# 02_main.net
KiCad netlist of a schematic drawn in Altium Designer
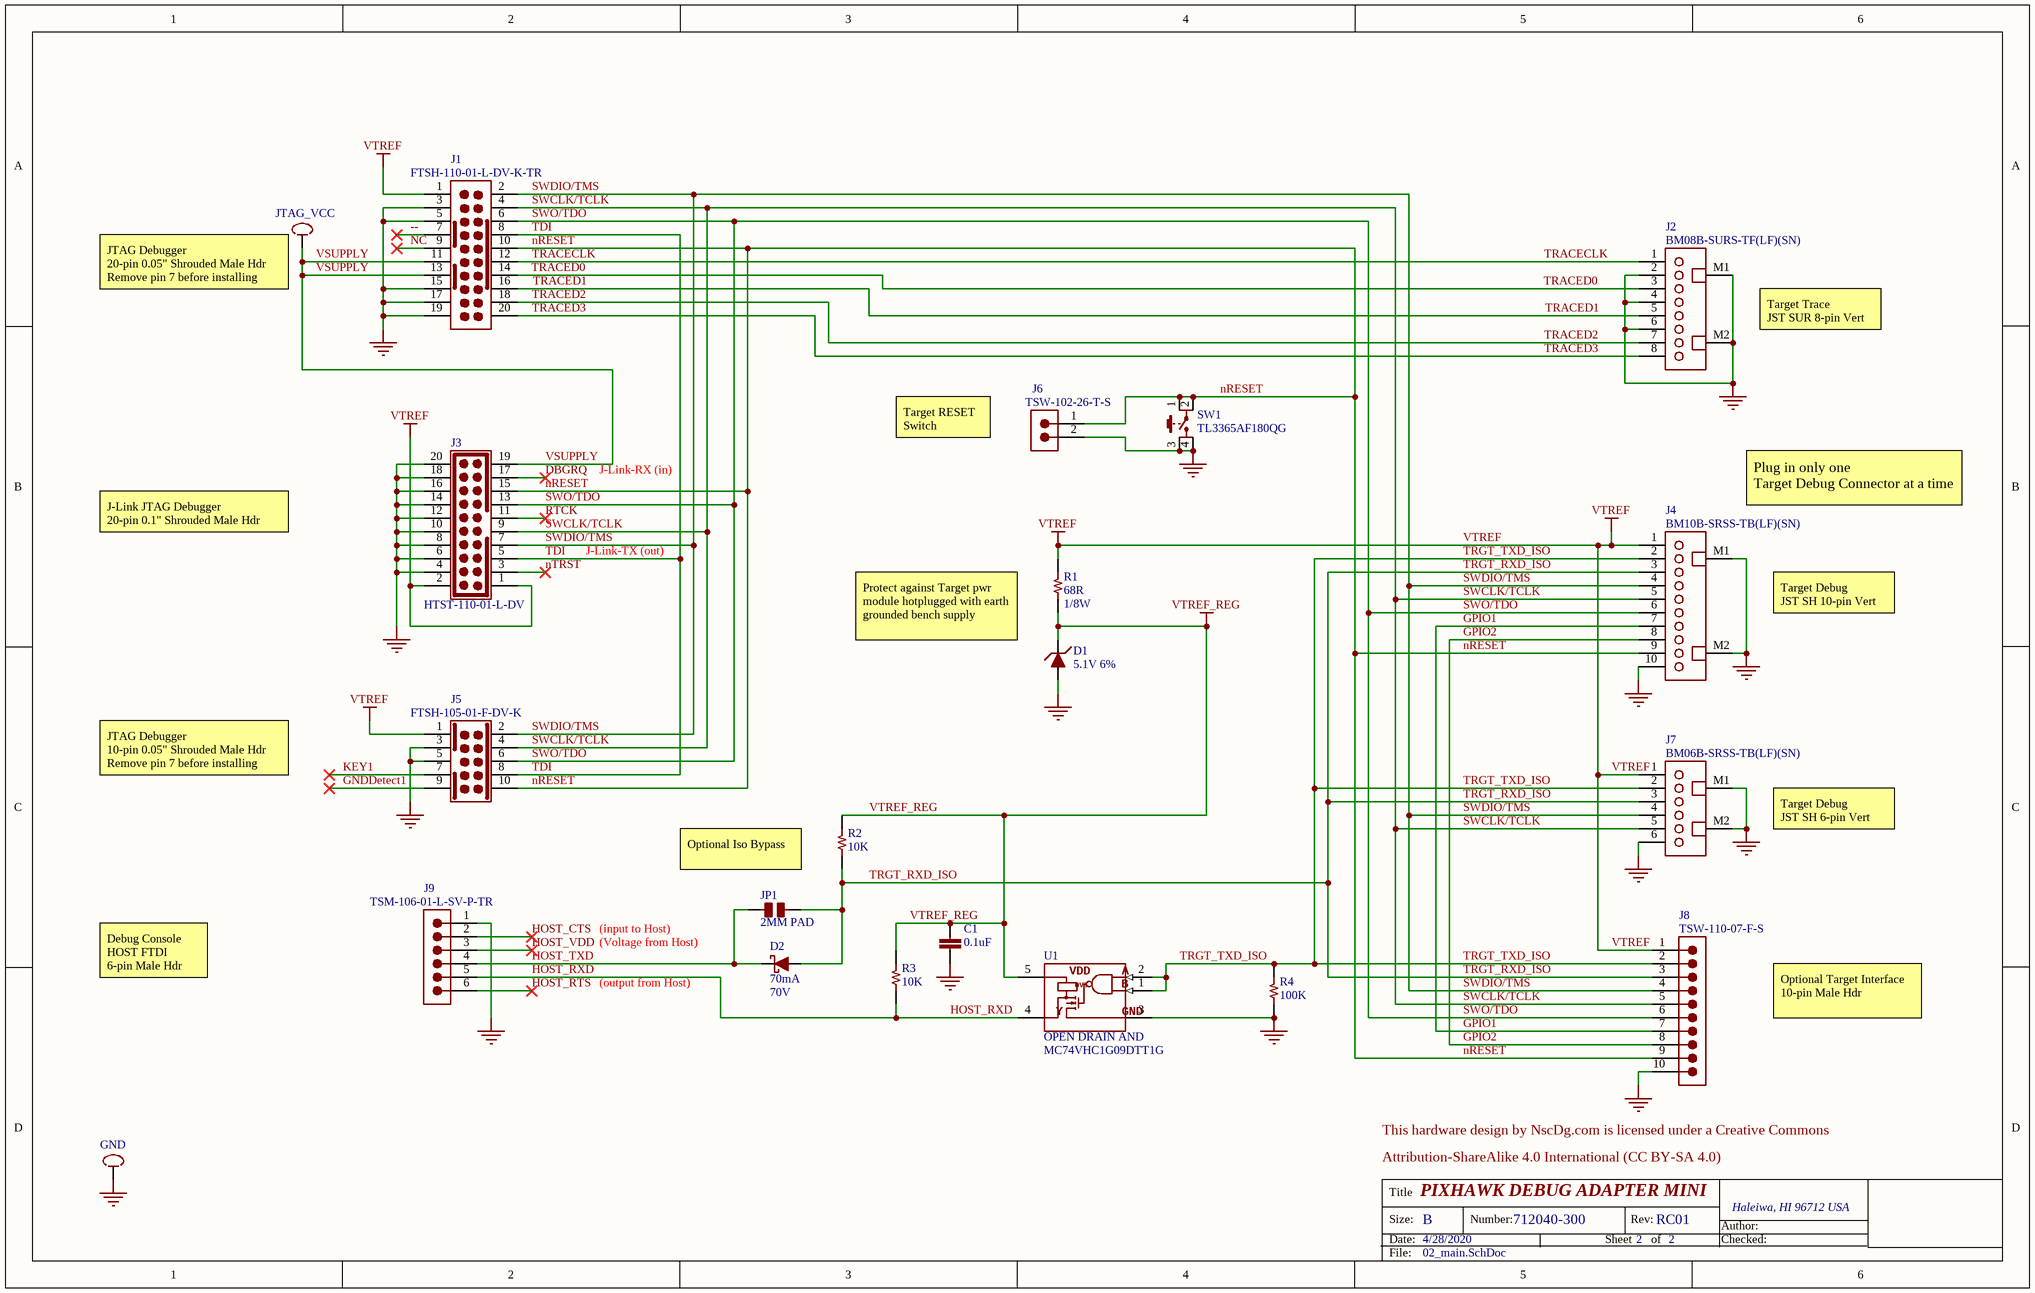
[diagram p0: 02_main.SchDoc]

(export (version "E")
  (design (tool "Eeschema 10.0.6"))
  (components
    (comp (ref "C1")
      (value "0.1uF")
      (footprint "CAPC100X50X56L25N")
      (description "CAP CER 0.1UF 10% 50V X5R 0402")
      (fields
        (field (name "TOLERANCE") "±10%")
        (field (name "MANUFACTURER") "Murata Electronics North America")
      )
      (libsource (lib "My_Integrated_Library") (part "CAP_0U1_50V_X5R_0402"))
    )
    (comp (ref "D1")
      (value "DIODE ZENER 5.1V 225MW SOT23-3")
      (footprint "SOT23-3P95_230X110L30X43N_DIODE")
      (fields
        (field (name "MANUFACTURER") "ON Semiconductor")
        (field (name "MANUFACTURER PART NUMBER") "BZX84C5V1LT3G")
        (field (name "ID") "5.1V 6%")
      )
      (libsource (lib "My_Integrated_Library") (part "DIODE_ZENER_5.1V_SOT23-3"))
    )
    (comp (ref "D2")
      (value "DIODE SCHOTTKY 70V 70MA SOD523")
      (footprint "SODFL120X80X70L30X30")
      (fields
        (field (name "MANUFACTURER") "STMicroelectronics")
        (field (name "MANUFACTURER PART NUMBER") "BAS70KFILM")
        (field (name "CURRENT") "70mA")
        (field (name "VOLTAGE") "70V")
      )
      (libsource (lib "My_Integrated_Library") (part "DIODE_SCHOTTKY_BAS70_SOD523_SMT"))
    )
    (comp (ref "GND")
      (value "TESTPOINT MINIATURE SMD")
      (footprint "KSTN-5015")
      (fields
        (field (name "MANUFACTURER") "Keystone Electronics")
        (field (name "MANUFACTURER PART NUMBER") "5015")
      )
      (libsource (lib "My_Integrated_Library") (part "TESTPOINT_MINIATURE_SMD"))
    )
    (comp (ref "J1")
      (value "CONN_HDR_2X10_VERT_SHROUD_FTSH_1.27MM_SMT")
      (footprint "SAMTEC_FTSH-110-01-L-DV-K-TR")
      (fields
        (field (name "MANUFACTURER") "Samtec Inc.")
        (field (name "MANUFACTURER PART NUMBER") "FTSH-110-01-L-DV-K-TR")
      )
      (libsource (lib "My_Integrated_Library") (part "CONN_HDR_2X10_SHROUD_1.27MM_SMT"))
    )
    (comp (ref "J2")
      (value "CONN HEADER SUR 8POS .8MM VERT SMT")
      (footprint "JST_BM08B-SURS-TFLFSN")
      (fields
        (field (name "MANUFACTURER") "JST Sales America Inc.")
        (field (name "MANUFACTURER PART NUMBER") "BM08B-SURS-TF(LF)(SN)")
      )
      (libsource (lib "My_Integrated_Library") (part "CONN_JST_SUR_8PIN_VERT_SMT"))
    )
    (comp (ref "J3")
      (value "CONN_HDR_2X10_MALE_2.54MM_SHR_SAMTEC_SMD")
      (footprint "SAMTEC_HTST-110-01-F-DV")
      (fields
        (field (name "MANUFACTURER") "Samtec Inc.")
        (field (name "MANUFACTURER PART NUMBER") "HTST-110-01-L-DV")
      )
      (libsource (lib "My_Integrated_Library") (part "CONN_HDR_2X10_MALE_2.54MM_SHR_SAMTEC_SMD"))
    )
    (comp (ref "J4")
      (value "CONN HEADER SH 10POS TOP 1MM TIN")
      (footprint "JST_BM10B-SRSS-TB")
      (fields
        (field (name "MANUFACTURER") "JST Sales America Inc.")
        (field (name "MANUFACTURER PART NUMBER") "BM10B-SRSS-TB(LF)(SN)")
      )
      (libsource (lib "My_Integrated_Library") (part "CONN_JST_SH_10PIN_VERT_SMT"))
    )
    (comp (ref "J5")
      (value "CONN HEADER 10POS DUAL .05\" SMD")
      (footprint "FTSH-105-01-XXX-DV-K")
      (fields
        (field (name "MANUFACTURER") "Samtec Inc.")
        (field (name "MANUFACTURER PART NUMBER") "FTSH-105-01-F-DV-K")
      )
      (libsource (lib "My_Integrated_Library") (part "CONN_HDR_2X5_MALE_1.27MM_SMT"))
    )
    (comp (ref "J6")
      (value "CONN HEADER 2POS 0.100\" (2.54mm) TH")
      (footprint "SMTC-TSW-102-26-XX-S")
      (fields
        (field (name "MANUFACTURER") "Samtec Inc.")
        (field (name "MANUFACTURER PART NUMBER") "TSW-102-26-T-S")
      )
      (libsource (lib "My_Integrated_Library") (part "CONN_HDR_1X2_MALE_2.54MM_TH"))
    )
    (comp (ref "J7")
      (value "CONN HEADER SH 6POS TOP 1MM TIN")
      (footprint "JST_BM06B-SRSS-TB")
      (fields
        (field (name "MANUFACTURER") "JST Sales America Inc.")
        (field (name "MANUFACTURER PART NUMBER") "BM06B-SRSS-TB(LF)(SN)")
      )
      (libsource (lib "My_Integrated_Library") (part "CONN_JST_SH_6PIN_VERT_SMT"))
    )
    (comp (ref "J8")
      (value "CONN HEADER 0.100\" (2.54mm) 10POS VERT TH")
      (footprint "HDRV10W64P254_10X1_2054X254H851")
      (fields
        (field (name "MANUFACTURER") "Samtec")
        (field (name "MANUFACTURER PART NUMBER") "TSW-110-07-F-S")
      )
      (libsource (lib "My_Integrated_Library") (part "CONN_HDR_1X10_MALE_2.54MM_TH"))
    )
    (comp (ref "J9")
      (value "CONN HEADER 6POS 0.100\" (2.54mm) SMD")
      (footprint "SAMTEC_TSM-106-01-XX-SV")
      (fields
        (field (name "MANUFACTURER") "Samtec")
        (field (name "MANUFACTURER PART NUMBER") "TSM-106-01-L-SV-P-TR")
      )
      (libsource (lib "My_Integrated_Library") (part "CONN_HDR_1X6_MALE_2.54MM_SMD"))
    )
    (comp (ref "JP1")
      (value "JUMPER SHORTING BAR 2MM PAD")
      (footprint "SHORTING_JUMPER_2MM")
      (fields (field (name "PARAMETER") "2MM PAD"))
      (libsource (lib "My_Integrated_Library") (part "JUMPER_SHORTING_BAR_2MM_PAD"))
    )
    (comp (ref "JTAG_VCC")
      (value "TESTPOINT MINIATURE SMD")
      (footprint "KSTN-5015")
      (fields
        (field (name "MANUFACTURER") "Keystone Electronics")
        (field (name "MANUFACTURER PART NUMBER") "5015")
      )
      (libsource (lib "My_Integrated_Library") (part "TESTPOINT_MINIATURE_SMD"))
    )
    (comp (ref "R1")
      (value "68R")
      (footprint "RESC200X125X70L40N")
      (description "RES SMD 68 OHM 1% 1/8W 0805")
      (fields
        (field (name "TOLERANCE") "±1%")
        (field (name "MANUFACTURER") "Yageo")
        (field (name "POWER") "1/8W")
      )
      (libsource (lib "My_Integrated_Library") (part "RES_68R_1%_1/8W_0805"))
    )
    (comp (ref "R2")
      (value "10K")
      (footprint "RESC100X50X40L25")
      (description "RES SMD 10K OHM 1% 1/16W 0402")
      (fields (field (name "TOLERANCE") "±1%") (field (name "MANUFACTURER") "Yageo"))
      (libsource (lib "My_Integrated_Library") (part "RES_10K_1%_1/16W_0402"))
    )
    (comp (ref "R3")
      (value "10K")
      (footprint "RESC100X50X40L25")
      (description "RES SMD 10K OHM 1% 1/16W 0402")
      (fields (field (name "TOLERANCE") "±1%") (field (name "MANUFACTURER") "Yageo"))
      (libsource (lib "My_Integrated_Library") (part "RES_10K_1%_1/16W_0402"))
    )
    (comp (ref "R4")
      (value "100K")
      (footprint "RESC100X50X40L25")
      (description "RES SMD 100K OHM 1% 1/16W 0402")
      (fields (field (name "TOLERANCE") "±1%") (field (name "MANUFACTURER") "Yageo"))
      (libsource (lib "My_Integrated_Library") (part "RES_100K_1%_1/16W_0402"))
    )
    (comp (ref "SW1")
      (value "SWITCH TACTILE SPST-NO 0.05A 12V SMT")
      (footprint "SWITCH_SON4P450_420X320X250L75X100N")
      (fields
        (field (name "MANUFACTURER") "E-Switch")
        (field (name "MANUFACTURER PART NUMBER") "TL3365AF180QG")
      )
      (libsource (lib "My_Integrated_Library") (part "SWITCH_SPST_OFF_MOM_NO_SMT"))
    )
    (comp (ref "U1")
      (value "IC GATE AND 1CH 2-INP 5-TSOP")
      (footprint "SOT23-5P95_270X145L35X35N")
      (fields
        (field (name "MANUFACTURER") "ON Semiconductor")
        (field (name "ID") "OPEN DRAIN AND")
        (field (name "MANUFACTURER PART NUMBER") "MC74VHC1G09DTT1G")
      )
      (libsource (lib "My_Integrated_Library") (part "IC_GATE_SINGLE_AND_OPEN_DRAIN_5-TSOP"))
    )
  )
  (nets
    (net (code "1") (name "/--") (class "Default")
      (node (ref "J1") (pin "7") (pinfunction "7_7") (pintype "passive+no_connect"))
    )
    (net (code "2") (name "/DBGRQ") (class "Default")
      (node (ref "J3") (pin "17") (pinfunction "17_17") (pintype "passive+no_connect"))
    )
    (net (code "3") (name "/GNDDetect1") (class "Default")
      (node (ref "J5") (pin "9") (pinfunction "9_9") (pintype "passive+no_connect"))
    )
    (net (code "4") (name "/GPIO1") (class "Default")
      (node (ref "J4") (pin "7") (pinfunction "7_7") (pintype "passive"))
      (node (ref "J8") (pin "7") (pinfunction "7_7") (pintype "passive"))
    )
    (net (code "5") (name "/GPIO2") (class "Default")
      (node (ref "J4") (pin "8") (pinfunction "8_8") (pintype "passive"))
      (node (ref "J8") (pin "8") (pinfunction "8_8") (pintype "passive"))
    )
    (net (code "6") (name "/HOST_CTS") (class "Default")
      (node (ref "J9") (pin "2") (pinfunction "2_2") (pintype "passive+no_connect"))
    )
    (net (code "7") (name "/HOST_RTS") (class "Default")
      (node (ref "J9") (pin "6") (pinfunction "6_6") (pintype "passive+no_connect"))
    )
    (net (code "8") (name "/HOST_RXD") (class "Default")
      (node (ref "J9") (pin "5") (pinfunction "5_5") (pintype "passive"))
      (node (ref "R3") (pin "2") (pinfunction "2_2") (pintype "passive"))
      (node (ref "U1") (pin "4") (pinfunction "Y_4") (pintype "open_collector"))
    )
    (net (code "9") (name "/HOST_TXD") (class "Default")
      (node (ref "D2") (pin "C") (pinfunction "C_C") (pintype "passive"))
      (node (ref "J9") (pin "4") (pinfunction "4_4") (pintype "passive"))
      (node (ref "JP1") (pin "1") (pinfunction "1_1") (pintype "passive"))
    )
    (net (code "10") (name "/HOST_VDD") (class "Default")
      (node (ref "J9") (pin "3") (pinfunction "3_3") (pintype "passive+no_connect"))
    )
    (net (code "11") (name "/KEY1") (class "Default")
      (node (ref "J5") (pin "7") (pinfunction "7_7") (pintype "passive+no_connect"))
    )
    (net (code "12") (name "/NC") (class "Default")
      (node (ref "J1") (pin "9") (pinfunction "9_9") (pintype "passive+no_connect"))
    )
    (net (code "13") (name "/RTCK") (class "Default")
      (node (ref "J3") (pin "11") (pinfunction "11_11") (pintype "passive+no_connect"))
    )
    (net (code "14") (name "/SWCLK{slash}TCLK") (class "Default")
      (node (ref "J1") (pin "4") (pinfunction "4_4") (pintype "passive"))
      (node (ref "J3") (pin "9") (pinfunction "9_9") (pintype "passive"))
      (node (ref "J4") (pin "5") (pinfunction "5_5") (pintype "passive"))
      (node (ref "J5") (pin "4") (pinfunction "4_4") (pintype "passive"))
      (node (ref "J7") (pin "5") (pinfunction "5_5") (pintype "passive"))
      (node (ref "J8") (pin "5") (pinfunction "5_5") (pintype "passive"))
    )
    (net (code "15") (name "/SWDIO{slash}TMS") (class "Default")
      (node (ref "J1") (pin "2") (pinfunction "2_2") (pintype "passive"))
      (node (ref "J3") (pin "7") (pinfunction "7_7") (pintype "passive"))
      (node (ref "J4") (pin "4") (pinfunction "4_4") (pintype "passive"))
      (node (ref "J5") (pin "2") (pinfunction "2_2") (pintype "passive"))
      (node (ref "J7") (pin "4") (pinfunction "4_4") (pintype "passive"))
      (node (ref "J8") (pin "4") (pinfunction "4_4") (pintype "passive"))
    )
    (net (code "16") (name "/SWO{slash}TDO") (class "Default")
      (node (ref "J1") (pin "6") (pinfunction "6_6") (pintype "passive"))
      (node (ref "J3") (pin "13") (pinfunction "13_13") (pintype "passive"))
      (node (ref "J4") (pin "6") (pinfunction "6_6") (pintype "passive"))
      (node (ref "J5") (pin "6") (pinfunction "6_6") (pintype "passive"))
      (node (ref "J8") (pin "6") (pinfunction "6_6") (pintype "passive"))
    )
    (net (code "17") (name "/TDI") (class "Default")
      (node (ref "J1") (pin "8") (pinfunction "8_8") (pintype "passive"))
      (node (ref "J3") (pin "5") (pinfunction "5_5") (pintype "passive"))
      (node (ref "J5") (pin "8") (pinfunction "8_8") (pintype "passive"))
    )
    (net (code "18") (name "/TRACECLK") (class "Default")
      (node (ref "J1") (pin "12") (pinfunction "12_12") (pintype "passive"))
      (node (ref "J2") (pin "1") (pinfunction "1_1") (pintype "passive"))
    )
    (net (code "19") (name "/TRACED0") (class "Default")
      (node (ref "J1") (pin "14") (pinfunction "14_14") (pintype "passive"))
      (node (ref "J2") (pin "3") (pinfunction "3_3") (pintype "passive"))
    )
    (net (code "20") (name "/TRACED1") (class "Default")
      (node (ref "J1") (pin "16") (pinfunction "16_16") (pintype "passive"))
      (node (ref "J2") (pin "5") (pinfunction "5_5") (pintype "passive"))
    )
    (net (code "21") (name "/TRACED2") (class "Default")
      (node (ref "J1") (pin "18") (pinfunction "18_18") (pintype "passive"))
      (node (ref "J2") (pin "7") (pinfunction "7_7") (pintype "passive"))
    )
    (net (code "22") (name "/TRACED3") (class "Default")
      (node (ref "J1") (pin "20") (pinfunction "20_20") (pintype "passive"))
      (node (ref "J2") (pin "8") (pinfunction "8_8") (pintype "passive"))
    )
    (net (code "23") (name "/TRGT_RXD_ISO") (class "Default")
      (node (ref "D2") (pin "A") (pinfunction "A_A") (pintype "passive"))
      (node (ref "J4") (pin "3") (pinfunction "3_3") (pintype "passive"))
      (node (ref "J7") (pin "3") (pinfunction "3_3") (pintype "passive"))
      (node (ref "J8") (pin "3") (pinfunction "3_3") (pintype "passive"))
      (node (ref "JP1") (pin "2") (pinfunction "2_2") (pintype "passive"))
      (node (ref "R2") (pin "2") (pinfunction "2_2") (pintype "passive"))
    )
    (net (code "24") (name "/TRGT_TXD_ISO") (class "Default")
      (node (ref "J4") (pin "2") (pinfunction "2_2") (pintype "passive"))
      (node (ref "J7") (pin "2") (pinfunction "2_2") (pintype "passive"))
      (node (ref "J8") (pin "2") (pinfunction "2_2") (pintype "passive"))
      (node (ref "R4") (pin "1") (pinfunction "1_1") (pintype "passive"))
      (node (ref "U1") (pin "1") (pinfunction "B_1") (pintype "input"))
      (node (ref "U1") (pin "2") (pinfunction "A_2") (pintype "input"))
    )
    (net (code "25") (name "/VSUPPLY") (class "Default")
      (node (ref "J1") (pin "11") (pinfunction "11_11") (pintype "passive"))
      (node (ref "J1") (pin "13") (pinfunction "13_13") (pintype "passive"))
      (node (ref "J3") (pin "19") (pinfunction "19_19") (pintype "passive"))
      (node (ref "JTAG_VCC") (pin "1") (pinfunction "1_1") (pintype "passive"))
    )
    (net (code "26") (name "/nRESET") (class "Default")
      (node (ref "J1") (pin "10") (pinfunction "10_10") (pintype "passive"))
      (node (ref "J3") (pin "15") (pinfunction "15_15") (pintype "passive"))
      (node (ref "J4") (pin "9") (pinfunction "9_9") (pintype "passive"))
      (node (ref "J5") (pin "10") (pinfunction "10_10") (pintype "passive"))
      (node (ref "J6") (pin "1") (pinfunction "1_1") (pintype "passive"))
      (node (ref "J8") (pin "9") (pinfunction "9_9") (pintype "passive"))
      (node (ref "SW1") (pin "1") (pinfunction "1_1") (pintype "passive"))
      (node (ref "SW1") (pin "2") (pinfunction "2_2") (pintype "passive"))
    )
    (net (code "27") (name "/nTRST") (class "Default")
      (node (ref "J3") (pin "3") (pinfunction "3_3") (pintype "passive+no_connect"))
    )
    (net (code "28") (name "GND") (class "Default")
      (node (ref "C1") (pin "2") (pinfunction "2_2") (pintype "passive"))
      (node (ref "D1") (pin "1") (pinfunction "A_1") (pintype "passive"))
      (node (ref "GND") (pin "1") (pinfunction "1_1") (pintype "passive"))
      (node (ref "J1") (pin "15") (pinfunction "15_15") (pintype "passive"))
      (node (ref "J1") (pin "17") (pinfunction "17_17") (pintype "passive"))
      (node (ref "J1") (pin "19") (pinfunction "19_19") (pintype "passive"))
      (node (ref "J1") (pin "3") (pinfunction "3_3") (pintype "passive"))
      (node (ref "J1") (pin "5") (pinfunction "5_5") (pintype "passive"))
      (node (ref "J2") (pin "2") (pinfunction "2_2") (pintype "passive"))
      (node (ref "J2") (pin "4") (pinfunction "4_4") (pintype "passive"))
      (node (ref "J2") (pin "6") (pinfunction "6_6") (pintype "passive"))
      (node (ref "J2") (pin "M1") (pinfunction "M1_M1") (pintype "passive"))
      (node (ref "J2") (pin "M2") (pinfunction "M2_M2") (pintype "passive"))
      (node (ref "J3") (pin "10") (pinfunction "10_10") (pintype "passive"))
      (node (ref "J3") (pin "12") (pinfunction "12_12") (pintype "passive"))
      (node (ref "J3") (pin "14") (pinfunction "14_14") (pintype "passive"))
      (node (ref "J3") (pin "16") (pinfunction "16_16") (pintype "passive"))
      (node (ref "J3") (pin "18") (pinfunction "18_18") (pintype "passive"))
      (node (ref "J3") (pin "20") (pinfunction "20_20") (pintype "passive"))
      (node (ref "J3") (pin "4") (pinfunction "4_4") (pintype "passive"))
      (node (ref "J3") (pin "6") (pinfunction "6_6") (pintype "passive"))
      (node (ref "J3") (pin "8") (pinfunction "8_8") (pintype "passive"))
      (node (ref "J4") (pin "10") (pinfunction "10_10") (pintype "passive"))
      (node (ref "J4") (pin "M1") (pinfunction "M1_M1") (pintype "passive"))
      (node (ref "J4") (pin "M2") (pinfunction "M2_M2") (pintype "passive"))
      (node (ref "J5") (pin "3") (pinfunction "3_3") (pintype "passive"))
      (node (ref "J5") (pin "5") (pinfunction "5_5") (pintype "passive"))
      (node (ref "J6") (pin "2") (pinfunction "2_2") (pintype "passive"))
      (node (ref "J7") (pin "6") (pinfunction "6_6") (pintype "passive"))
      (node (ref "J7") (pin "M1") (pinfunction "M1_M1") (pintype "passive"))
      (node (ref "J7") (pin "M2") (pinfunction "M2_M2") (pintype "passive"))
      (node (ref "J8") (pin "10") (pinfunction "10_10") (pintype "passive"))
      (node (ref "J9") (pin "1") (pinfunction "1_1") (pintype "passive"))
      (node (ref "R4") (pin "2") (pinfunction "2_2") (pintype "passive"))
      (node (ref "SW1") (pin "3") (pinfunction "3_3") (pintype "passive"))
      (node (ref "SW1") (pin "4") (pinfunction "4_4") (pintype "passive"))
      (node (ref "U1") (pin "3") (pinfunction "GND_3") (pintype "power_in"))
    )
    (net (code "29") (name "VTREF") (class "Default")
      (node (ref "J1") (pin "1") (pinfunction "1_1") (pintype "passive"))
      (node (ref "J3") (pin "1") (pinfunction "1_1") (pintype "passive"))
      (node (ref "J3") (pin "2") (pinfunction "2_2") (pintype "passive"))
      (node (ref "J4") (pin "1") (pinfunction "1_1") (pintype "passive"))
      (node (ref "J5") (pin "1") (pinfunction "1_1") (pintype "passive"))
      (node (ref "J7") (pin "1") (pinfunction "1_1") (pintype "passive"))
      (node (ref "J8") (pin "1") (pinfunction "1_1") (pintype "passive"))
      (node (ref "R1") (pin "1") (pinfunction "1_1") (pintype "passive"))
    )
    (net (code "30") (name "VTREF_REG") (class "Default")
      (node (ref "C1") (pin "1") (pinfunction "1_1") (pintype "passive"))
      (node (ref "D1") (pin "3") (pinfunction "K_3") (pintype "passive"))
      (node (ref "R1") (pin "2") (pinfunction "2_2") (pintype "passive"))
      (node (ref "R2") (pin "1") (pinfunction "1_1") (pintype "passive"))
      (node (ref "R3") (pin "1") (pinfunction "1_1") (pintype "passive"))
      (node (ref "U1") (pin "5") (pinfunction "VDD_5") (pintype "power_in"))
    )
  )
)
